# Temperature_Beeper.net
KiCad netlist of a schematic drawn in EAGLE
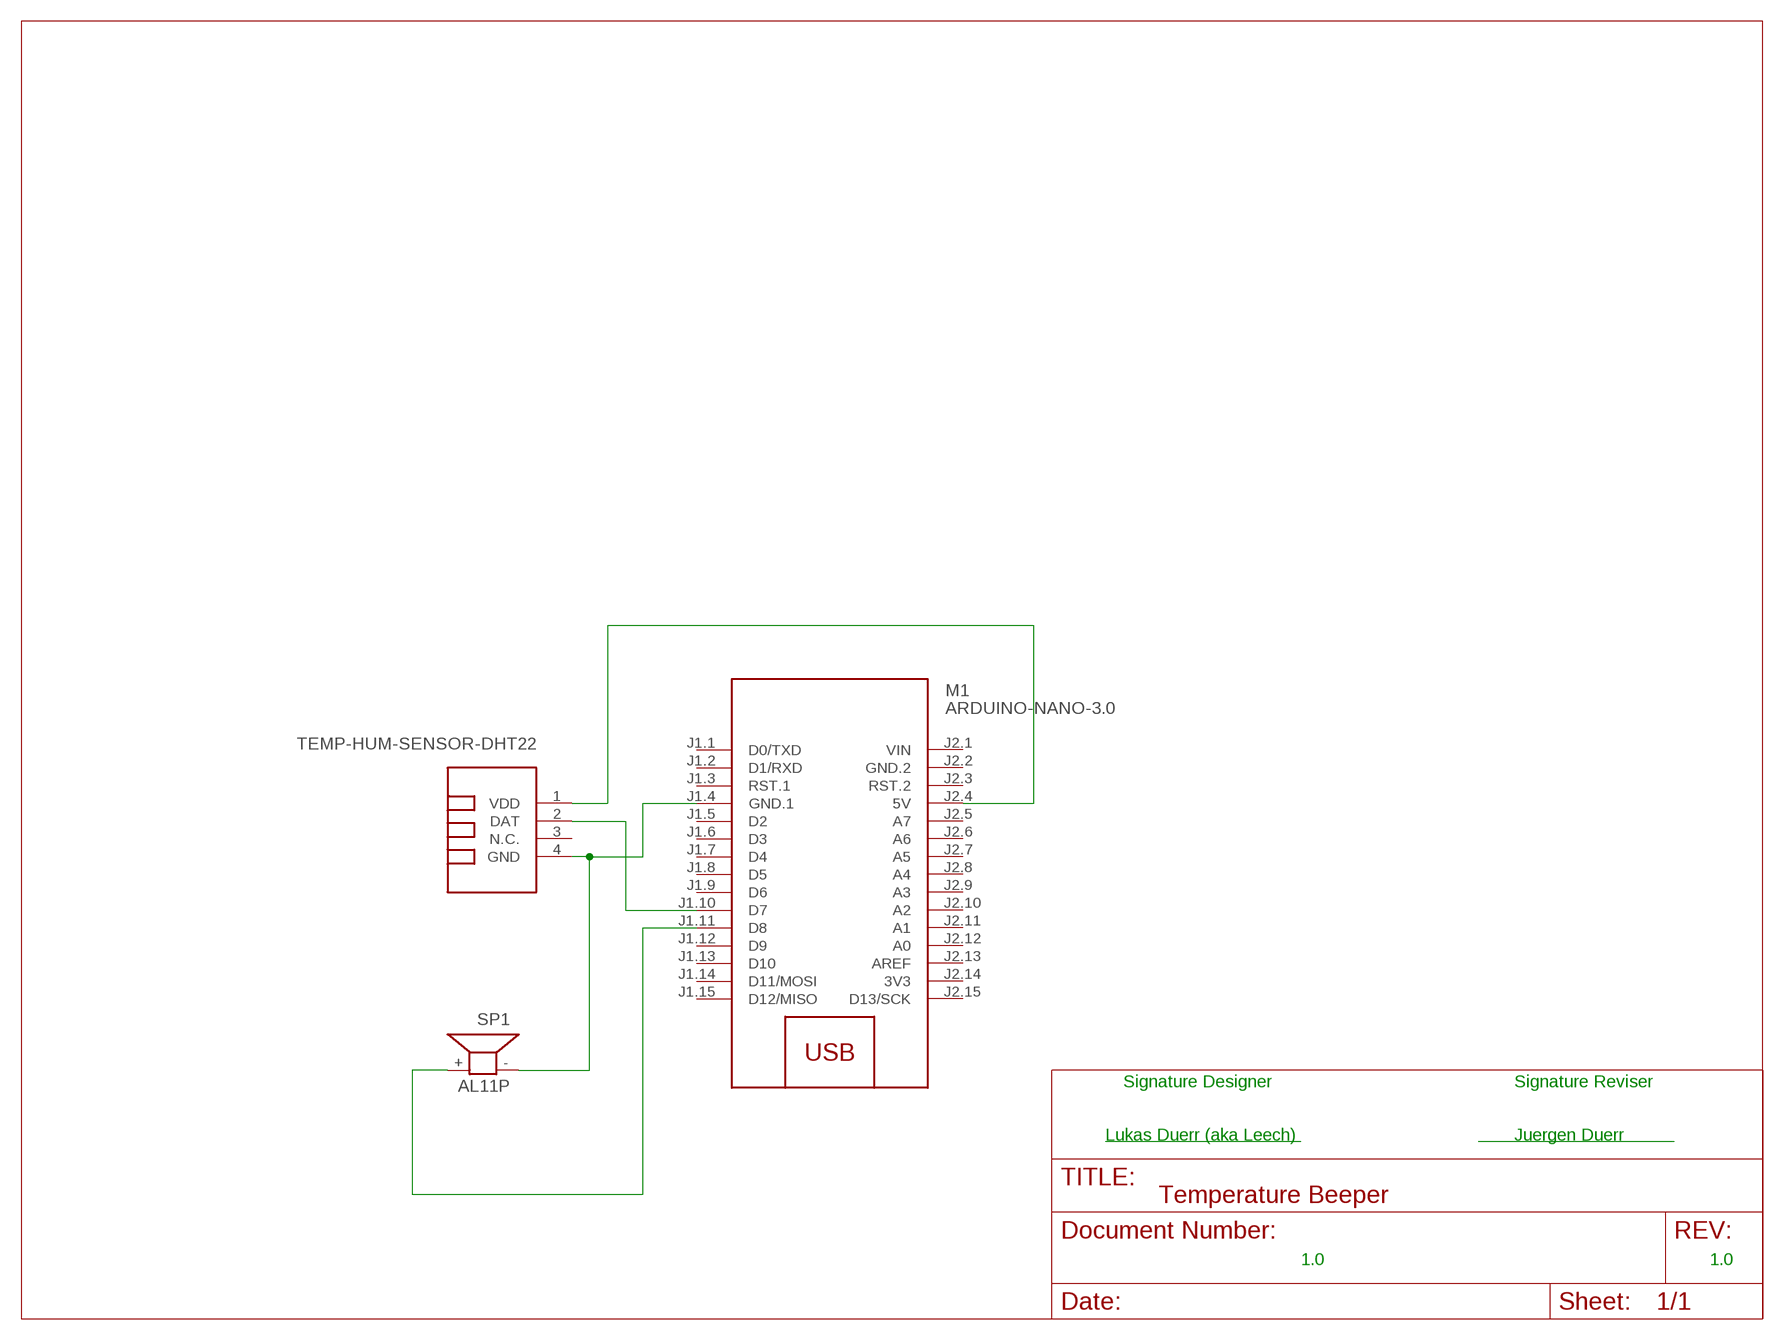
[diagram p0: schematic, sheet 1]

(export (version "E")
  (design (tool "Eeschema 10.0.6"))
  (components
    (comp (ref "M1")
      (value "ARDUINO-NANO-3.0")
      (footprint "eagle-import:ARDUINO-NANO-3.0")
      (libsource (lib "eagle-import") (part "ARDUINO-NANO-3.0"))
    )
    (comp (ref "SP1")
      (value "AL11P")
      (footprint "eagle-import:AL11P")
      (libsource (lib "eagle-import") (part "AL11P"))
    )
    (comp (ref "U$2")
      (value "TEMP-HUM-SENSOR-DHT22")
      (footprint "eagle-import:TEMP-HUM-SENSOR-DHT22")
      (libsource (lib "eagle-import") (part "TEMP-HUM-SENSOR-DHT22"))
    )
  )
  (nets
    (net (code "1") (name "/3V3") (class "Default")
      (node (ref "M1") (pin "J2.14") (pinfunction "3V3_J2.14") (pintype "power_in"))
    )
    (net (code "2") (name "/GND.2") (class "Default")
      (node (ref "M1") (pin "J2.2") (pinfunction "GND.2_J2.2") (pintype "power_in"))
    )
    (net (code "3") (name "/VIN") (class "Default")
      (node (ref "M1") (pin "J2.1") (pinfunction "VIN_J2.1") (pintype "power_in"))
    )
    (net (code "4") (name "Net-(M1-5V)") (class "Default")
      (node (ref "M1") (pin "J2.4") (pinfunction "5V_J2.4") (pintype "power_in"))
      (node (ref "U$2") (pin "1") (pinfunction "VDD_1") (pintype "power_in"))
    )
    (net (code "5") (name "Net-(M1-D7)") (class "Default")
      (node (ref "M1") (pin "J1.10") (pinfunction "D7_J1.10") (pintype "bidirectional"))
      (node (ref "U$2") (pin "2") (pinfunction "DAT_2") (pintype "bidirectional"))
    )
    (net (code "6") (name "Net-(M1-D8)") (class "Default")
      (node (ref "M1") (pin "J1.11") (pinfunction "D8_J1.11") (pintype "bidirectional"))
      (node (ref "SP1") (pin "+") (pinfunction "2_+") (pintype "passive"))
    )
    (net (code "7") (name "Net-(M1-GND.1)") (class "Default")
      (node (ref "M1") (pin "J1.4") (pinfunction "GND.1_J1.4") (pintype "power_in"))
      (node (ref "SP1") (pin "-") (pinfunction "1_-") (pintype "passive"))
      (node (ref "U$2") (pin "4") (pinfunction "GND_4") (pintype "power_in"))
    )
    (net (code "8") (name "unconnected-(M1-A0-PadJ2.12)") (class "Default")
      (node (ref "M1") (pin "J2.12") (pinfunction "A0_J2.12") (pintype "bidirectional"))
    )
    (net (code "9") (name "unconnected-(M1-A1-PadJ2.11)") (class "Default")
      (node (ref "M1") (pin "J2.11") (pinfunction "A1_J2.11") (pintype "bidirectional"))
    )
    (net (code "10") (name "unconnected-(M1-A2-PadJ2.10)") (class "Default")
      (node (ref "M1") (pin "J2.10") (pinfunction "A2_J2.10") (pintype "bidirectional"))
    )
    (net (code "11") (name "unconnected-(M1-A3-PadJ2.9)") (class "Default")
      (node (ref "M1") (pin "J2.9") (pinfunction "A3_J2.9") (pintype "bidirectional"))
    )
    (net (code "12") (name "unconnected-(M1-A4-PadJ2.8)") (class "Default")
      (node (ref "M1") (pin "J2.8") (pinfunction "A4_J2.8") (pintype "bidirectional"))
    )
    (net (code "13") (name "unconnected-(M1-A5-PadJ2.7)") (class "Default")
      (node (ref "M1") (pin "J2.7") (pinfunction "A5_J2.7") (pintype "bidirectional"))
    )
    (net (code "14") (name "unconnected-(M1-A6-PadJ2.6)") (class "Default")
      (node (ref "M1") (pin "J2.6") (pinfunction "A6_J2.6") (pintype "bidirectional"))
    )
    (net (code "15") (name "unconnected-(M1-A7-PadJ2.5)") (class "Default")
      (node (ref "M1") (pin "J2.5") (pinfunction "A7_J2.5") (pintype "bidirectional"))
    )
    (net (code "16") (name "unconnected-(M1-AREF-PadJ2.13)") (class "Default")
      (node (ref "M1") (pin "J2.13") (pinfunction "AREF_J2.13") (pintype "bidirectional"))
    )
    (net (code "17") (name "unconnected-(M1-D0{slash}TXD-PadJ1.1)") (class "Default")
      (node (ref "M1") (pin "J1.1") (pinfunction "D0/TXD_J1.1") (pintype "bidirectional"))
    )
    (net (code "18") (name "unconnected-(M1-D1{slash}RXD-PadJ1.2)") (class "Default")
      (node (ref "M1") (pin "J1.2") (pinfunction "D1/RXD_J1.2") (pintype "bidirectional"))
    )
    (net (code "19") (name "unconnected-(M1-D2-PadJ1.5)") (class "Default")
      (node (ref "M1") (pin "J1.5") (pinfunction "D2_J1.5") (pintype "bidirectional"))
    )
    (net (code "20") (name "unconnected-(M1-D3-PadJ1.6)") (class "Default")
      (node (ref "M1") (pin "J1.6") (pinfunction "D3_J1.6") (pintype "bidirectional"))
    )
    (net (code "21") (name "unconnected-(M1-D4-PadJ1.7)") (class "Default")
      (node (ref "M1") (pin "J1.7") (pinfunction "D4_J1.7") (pintype "bidirectional"))
    )
    (net (code "22") (name "unconnected-(M1-D5-PadJ1.8)") (class "Default")
      (node (ref "M1") (pin "J1.8") (pinfunction "D5_J1.8") (pintype "bidirectional"))
    )
    (net (code "23") (name "unconnected-(M1-D6-PadJ1.9)") (class "Default")
      (node (ref "M1") (pin "J1.9") (pinfunction "D6_J1.9") (pintype "bidirectional"))
    )
    (net (code "24") (name "unconnected-(M1-D9-PadJ1.12)") (class "Default")
      (node (ref "M1") (pin "J1.12") (pinfunction "D9_J1.12") (pintype "bidirectional"))
    )
    (net (code "25") (name "unconnected-(M1-D10-PadJ1.13)") (class "Default")
      (node (ref "M1") (pin "J1.13") (pinfunction "D10_J1.13") (pintype "bidirectional"))
    )
    (net (code "26") (name "unconnected-(M1-D11{slash}MOSI-PadJ1.14)") (class "Default")
      (node (ref "M1") (pin "J1.14") (pinfunction "D11/MOSI_J1.14") (pintype "bidirectional"))
    )
    (net (code "27") (name "unconnected-(M1-D12{slash}MISO-PadJ1.15)") (class "Default")
      (node (ref "M1") (pin "J1.15") (pinfunction "D12/MISO_J1.15") (pintype "bidirectional"))
    )
    (net (code "28") (name "unconnected-(M1-D13{slash}SCK-PadJ2.15)") (class "Default")
      (node (ref "M1") (pin "J2.15") (pinfunction "D13/SCK_J2.15") (pintype "bidirectional"))
    )
    (net (code "29") (name "unconnected-(M1-RST.1-PadJ1.3)") (class "Default")
      (node (ref "M1") (pin "J1.3") (pinfunction "RST.1_J1.3") (pintype "bidirectional"))
    )
    (net (code "30") (name "unconnected-(M1-RST.2-PadJ2.3)") (class "Default")
      (node (ref "M1") (pin "J2.3") (pinfunction "RST.2_J2.3") (pintype "bidirectional"))
    )
    (net (code "31") (name "unconnected-(U$2-N.C.-Pad3)") (class "Default")
      (node (ref "U$2") (pin "3") (pinfunction "N.C._3") (pintype "passive"))
    )
  )
)
